# datalogger.net
KiCad netlist of a schematic drawn in EAGLE
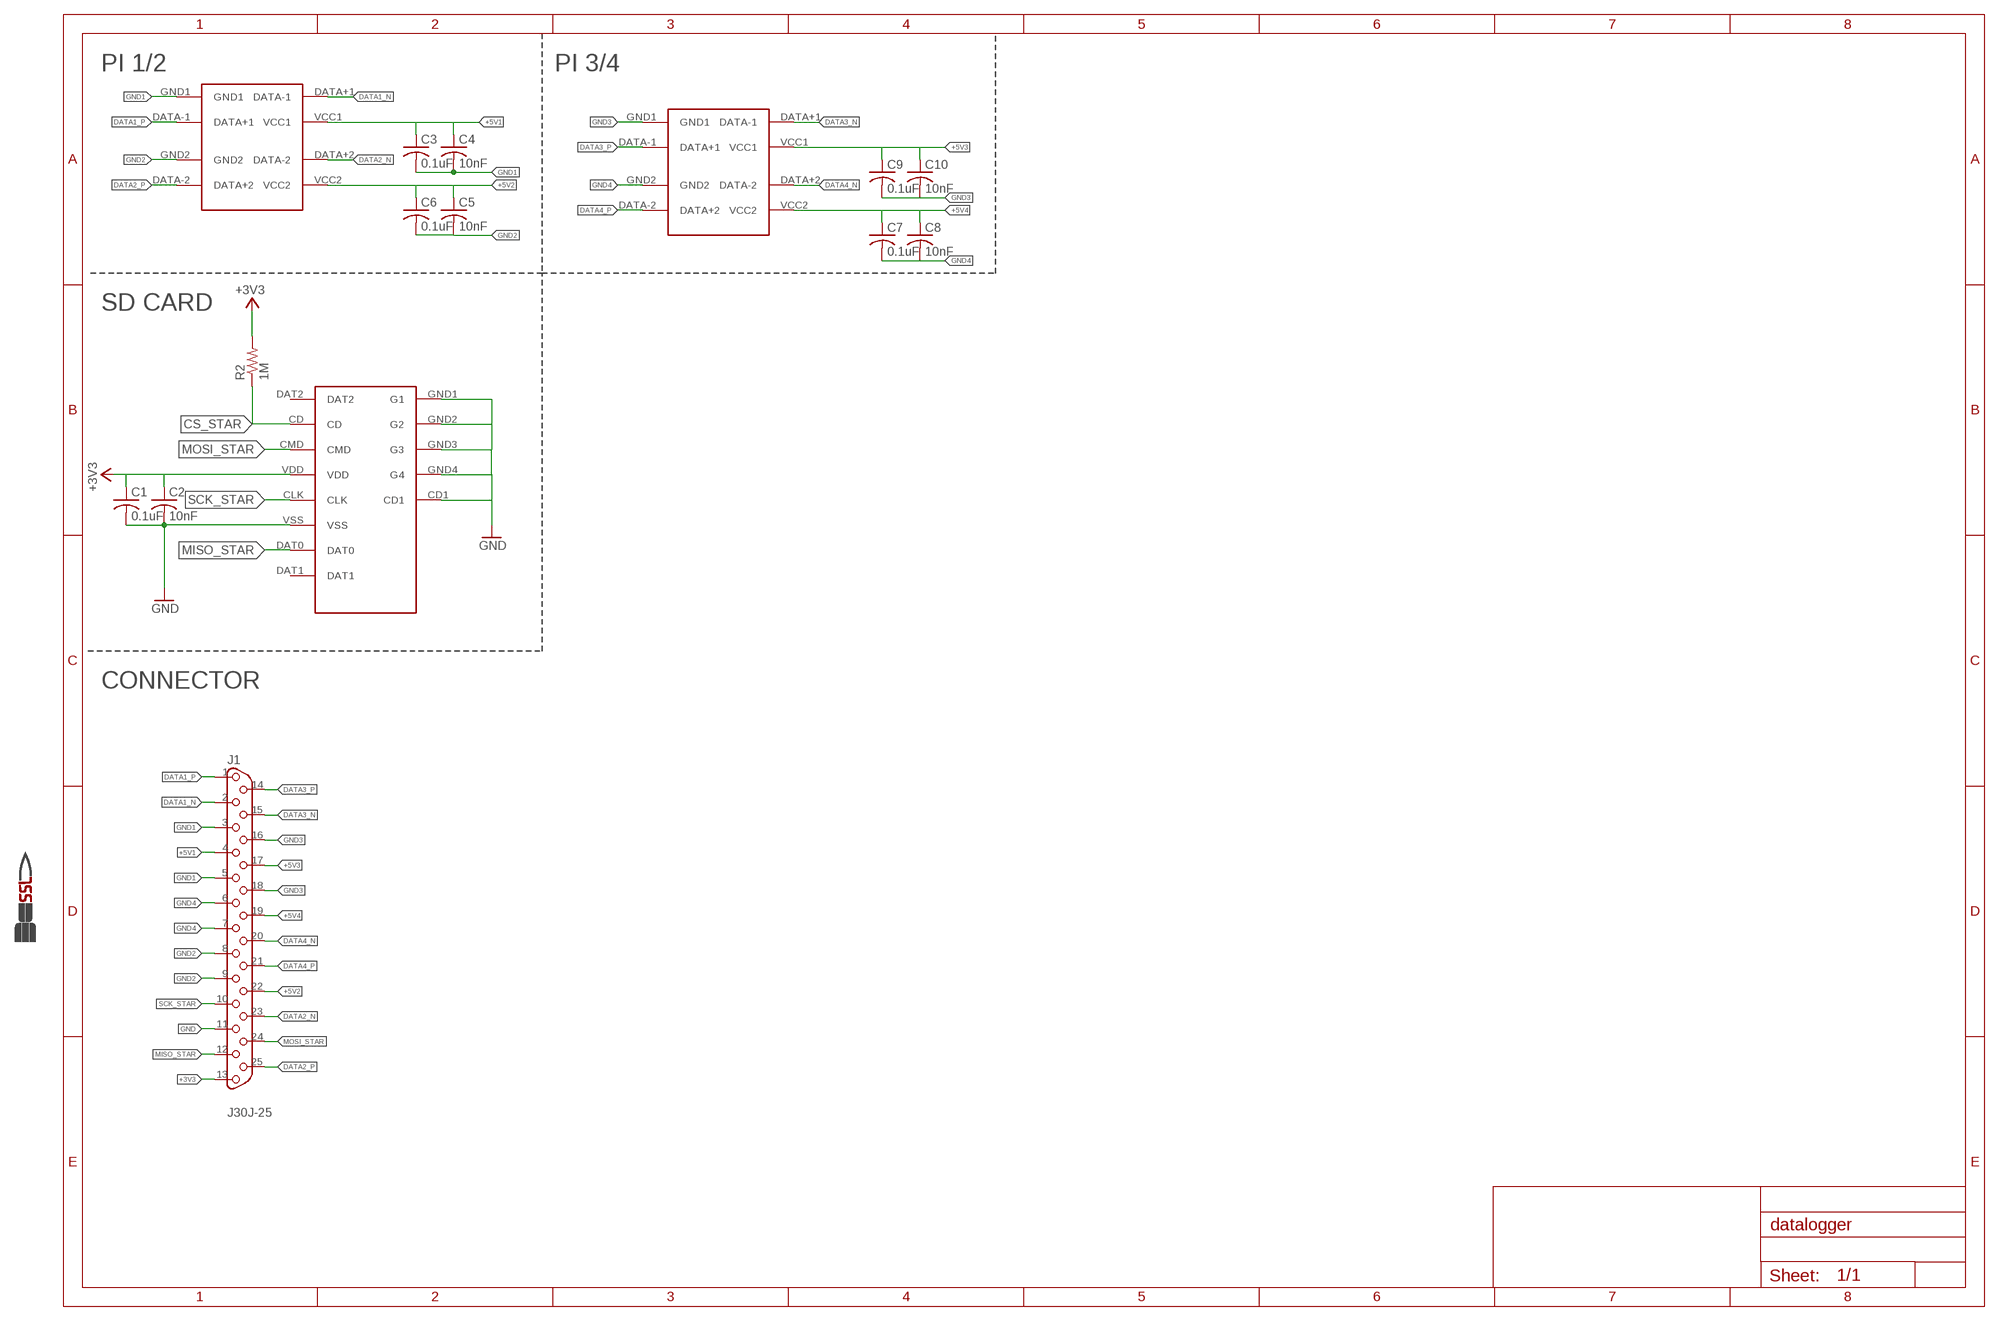
[diagram p0: schematic, sheet 1]

(export (version "E")
  (design (tool "Eeschema 10.0.6"))
  (components
    (comp (ref "C1")
      (value "0.1uF")
      (footprint "eagle-import:C0603")
      (libsource (lib "eagle-import") (part "C-USC0603"))
    )
    (comp (ref "C2")
      (value "10nF")
      (footprint "eagle-import:C0603")
      (libsource (lib "eagle-import") (part "C-USC0603"))
    )
    (comp (ref "C3")
      (value "0.1uF")
      (footprint "eagle-import:C0603")
      (libsource (lib "eagle-import") (part "C-USC0603"))
    )
    (comp (ref "C4")
      (value "10nF")
      (footprint "eagle-import:C0603")
      (libsource (lib "eagle-import") (part "C-USC0603"))
    )
    (comp (ref "C5")
      (value "10nF")
      (footprint "eagle-import:C0603")
      (libsource (lib "eagle-import") (part "C-USC0603"))
    )
    (comp (ref "C6")
      (value "0.1uF")
      (footprint "eagle-import:C0603")
      (libsource (lib "eagle-import") (part "C-USC0603"))
    )
    (comp (ref "C7")
      (value "0.1uF")
      (footprint "eagle-import:C0603")
      (libsource (lib "eagle-import") (part "C-USC0603"))
    )
    (comp (ref "C8")
      (value "10nF")
      (footprint "eagle-import:C0603")
      (libsource (lib "eagle-import") (part "C-USC0603"))
    )
    (comp (ref "C9")
      (value "0.1uF")
      (footprint "eagle-import:C0603")
      (libsource (lib "eagle-import") (part "C-USC0603"))
    )
    (comp (ref "C10")
      (value "10nF")
      (footprint "eagle-import:C0603")
      (libsource (lib "eagle-import") (part "C-USC0603"))
    )
    (comp (ref "GND1")
      (value "SSL.3IN_SILK")
      (footprint "eagle-import:SSL_SILK_.3IN")
      (libsource (lib "eagle-import") (part "SSL.3IN_SILK"))
    )
    (comp (ref "J1")
      (value "J30J-25")
      (footprint "eagle-import:ZKN-25")
      (libsource (lib "eagle-import") (part "J30J-25"))
    )
    (comp (ref "R2")
      (value "1M")
      (footprint "eagle-import:R0603")
      (libsource (lib "eagle-import") (part "R-US_R0603"))
    )
    (comp (ref "U$1")
      (value "MICRO_SD")
      (footprint "eagle-import:MICRO_SD_HINGED")
      (libsource (lib "eagle-import") (part "MICRO_SD"))
    )
    (comp (ref "U$2")
      (value "USB_A")
      (footprint "eagle-import:USB_A")
      (libsource (lib "eagle-import") (part "USB_A"))
    )
    (comp (ref "U$3")
      (value "USB_A")
      (footprint "eagle-import:USB_A")
      (libsource (lib "eagle-import") (part "USB_A"))
    )
  )
  (nets
    (net (code "1") (name "+3V3") (class "Default")
      (node (ref "C1") (pin "1") (pinfunction "1_1") (pintype "passive"))
      (node (ref "C2") (pin "1") (pinfunction "1_1") (pintype "passive"))
      (node (ref "J1") (pin "13") (pinfunction "13_13") (pintype "bidirectional"))
      (node (ref "R2") (pin "2") (pinfunction "2_2") (pintype "passive"))
      (node (ref "U$1") (pin "VDD") (pinfunction "VDD_VDD") (pintype "bidirectional"))
    )
    (net (code "2") (name "+5V1") (class "Default")
      (node (ref "C3") (pin "1") (pinfunction "1_1") (pintype "passive"))
      (node (ref "C4") (pin "1") (pinfunction "1_1") (pintype "passive"))
      (node (ref "J1") (pin "4") (pinfunction "4_4") (pintype "bidirectional"))
      (node (ref "U$2") (pin "VCC1") (pinfunction "VCC1_VCC1") (pintype "bidirectional"))
    )
    (net (code "3") (name "+5V2") (class "Default")
      (node (ref "C5") (pin "1") (pinfunction "1_1") (pintype "passive"))
      (node (ref "C6") (pin "1") (pinfunction "1_1") (pintype "passive"))
      (node (ref "J1") (pin "22") (pinfunction "22_22") (pintype "bidirectional"))
      (node (ref "U$2") (pin "VCC2") (pinfunction "VCC2_VCC2") (pintype "bidirectional"))
    )
    (net (code "4") (name "+5V3") (class "Default")
      (node (ref "C10") (pin "1") (pinfunction "1_1") (pintype "passive"))
      (node (ref "C9") (pin "1") (pinfunction "1_1") (pintype "passive"))
      (node (ref "J1") (pin "17") (pinfunction "17_17") (pintype "bidirectional"))
      (node (ref "U$3") (pin "VCC1") (pinfunction "VCC1_VCC1") (pintype "bidirectional"))
    )
    (net (code "5") (name "+5V4") (class "Default")
      (node (ref "C7") (pin "1") (pinfunction "1_1") (pintype "passive"))
      (node (ref "C8") (pin "1") (pinfunction "1_1") (pintype "passive"))
      (node (ref "J1") (pin "19") (pinfunction "19_19") (pintype "bidirectional"))
      (node (ref "U$3") (pin "VCC2") (pinfunction "VCC2_VCC2") (pintype "bidirectional"))
    )
    (net (code "6") (name "CS_STAR") (class "Default")
      (node (ref "R2") (pin "1") (pinfunction "1_1") (pintype "passive"))
      (node (ref "U$1") (pin "CD") (pinfunction "CD_CD") (pintype "bidirectional"))
    )
    (net (code "7") (name "DATA1_N") (class "Default")
      (node (ref "J1") (pin "2") (pinfunction "2_2") (pintype "bidirectional"))
      (node (ref "U$2") (pin "DATA+1") (pinfunction "DATA-1_DATA+1") (pintype "bidirectional"))
    )
    (net (code "8") (name "DATA1_P") (class "Default")
      (node (ref "J1") (pin "1") (pinfunction "1_1") (pintype "bidirectional"))
      (node (ref "U$2") (pin "DATA-1") (pinfunction "DATA+1_DATA-1") (pintype "bidirectional"))
    )
    (net (code "9") (name "DATA2_N") (class "Default")
      (node (ref "J1") (pin "23") (pinfunction "23_23") (pintype "bidirectional"))
      (node (ref "U$2") (pin "DATA+2") (pinfunction "DATA-2_DATA+2") (pintype "bidirectional"))
    )
    (net (code "10") (name "DATA2_P") (class "Default")
      (node (ref "J1") (pin "25") (pinfunction "25_25") (pintype "bidirectional"))
      (node (ref "U$2") (pin "DATA-2") (pinfunction "DATA+2_DATA-2") (pintype "bidirectional"))
    )
    (net (code "11") (name "DATA3_N") (class "Default")
      (node (ref "J1") (pin "15") (pinfunction "15_15") (pintype "bidirectional"))
      (node (ref "U$3") (pin "DATA+1") (pinfunction "DATA-1_DATA+1") (pintype "bidirectional"))
    )
    (net (code "12") (name "DATA3_P") (class "Default")
      (node (ref "J1") (pin "14") (pinfunction "14_14") (pintype "bidirectional"))
      (node (ref "U$3") (pin "DATA-1") (pinfunction "DATA+1_DATA-1") (pintype "bidirectional"))
    )
    (net (code "13") (name "DATA4_N") (class "Default")
      (node (ref "J1") (pin "20") (pinfunction "20_20") (pintype "bidirectional"))
      (node (ref "U$3") (pin "DATA+2") (pinfunction "DATA-2_DATA+2") (pintype "bidirectional"))
    )
    (net (code "14") (name "DATA4_P") (class "Default")
      (node (ref "J1") (pin "21") (pinfunction "21_21") (pintype "bidirectional"))
      (node (ref "U$3") (pin "DATA-2") (pinfunction "DATA+2_DATA-2") (pintype "bidirectional"))
    )
    (net (code "15") (name "GND") (class "Default")
      (node (ref "C1") (pin "2") (pinfunction "2_2") (pintype "passive"))
      (node (ref "C2") (pin "2") (pinfunction "2_2") (pintype "passive"))
      (node (ref "J1") (pin "11") (pinfunction "11_11") (pintype "bidirectional"))
      (node (ref "U$1") (pin "CD1") (pinfunction "CD1_CD1") (pintype "bidirectional"))
      (node (ref "U$1") (pin "GND1") (pinfunction "G1_GND1") (pintype "bidirectional"))
      (node (ref "U$1") (pin "GND2") (pinfunction "G2_GND2") (pintype "bidirectional"))
      (node (ref "U$1") (pin "GND3") (pinfunction "G3_GND3") (pintype "bidirectional"))
      (node (ref "U$1") (pin "GND4") (pinfunction "G4_GND4") (pintype "bidirectional"))
      (node (ref "U$1") (pin "VSS") (pinfunction "VSS_VSS") (pintype "bidirectional"))
    )
    (net (code "16") (name "GND1") (class "Default")
      (node (ref "C3") (pin "2") (pinfunction "2_2") (pintype "passive"))
      (node (ref "C4") (pin "2") (pinfunction "2_2") (pintype "passive"))
      (node (ref "J1") (pin "3") (pinfunction "3_3") (pintype "bidirectional"))
      (node (ref "J1") (pin "5") (pinfunction "5_5") (pintype "bidirectional"))
      (node (ref "U$2") (pin "GND1") (pinfunction "GND1_GND1") (pintype "bidirectional"))
    )
    (net (code "17") (name "GND2") (class "Default")
      (node (ref "C5") (pin "2") (pinfunction "2_2") (pintype "passive"))
      (node (ref "C6") (pin "2") (pinfunction "2_2") (pintype "passive"))
      (node (ref "J1") (pin "8") (pinfunction "8_8") (pintype "bidirectional"))
      (node (ref "J1") (pin "9") (pinfunction "9_9") (pintype "bidirectional"))
      (node (ref "U$2") (pin "GND2") (pinfunction "GND2_GND2") (pintype "bidirectional"))
    )
    (net (code "18") (name "GND3") (class "Default")
      (node (ref "C10") (pin "2") (pinfunction "2_2") (pintype "passive"))
      (node (ref "C9") (pin "2") (pinfunction "2_2") (pintype "passive"))
      (node (ref "J1") (pin "16") (pinfunction "16_16") (pintype "bidirectional"))
      (node (ref "J1") (pin "18") (pinfunction "18_18") (pintype "bidirectional"))
      (node (ref "U$3") (pin "GND1") (pinfunction "GND1_GND1") (pintype "bidirectional"))
    )
    (net (code "19") (name "GND4") (class "Default")
      (node (ref "C7") (pin "2") (pinfunction "2_2") (pintype "passive"))
      (node (ref "C8") (pin "2") (pinfunction "2_2") (pintype "passive"))
      (node (ref "J1") (pin "6") (pinfunction "6_6") (pintype "bidirectional"))
      (node (ref "J1") (pin "7") (pinfunction "7_7") (pintype "bidirectional"))
      (node (ref "U$3") (pin "GND2") (pinfunction "GND2_GND2") (pintype "bidirectional"))
    )
    (net (code "20") (name "MISO_STAR") (class "Default")
      (node (ref "J1") (pin "12") (pinfunction "12_12") (pintype "bidirectional"))
      (node (ref "U$1") (pin "DAT0") (pinfunction "DAT0_DAT0") (pintype "bidirectional"))
    )
    (net (code "21") (name "MOSI_STAR") (class "Default")
      (node (ref "J1") (pin "24") (pinfunction "24_24") (pintype "bidirectional"))
      (node (ref "U$1") (pin "CMD") (pinfunction "CMD_CMD") (pintype "bidirectional"))
    )
    (net (code "22") (name "SCK_STAR") (class "Default")
      (node (ref "J1") (pin "10") (pinfunction "10_10") (pintype "bidirectional"))
      (node (ref "U$1") (pin "CLK") (pinfunction "CLK_CLK") (pintype "bidirectional"))
    )
    (net (code "23") (name "unconnected-(U$1-PadDAT1)") (class "Default")
      (node (ref "U$1") (pin "DAT1") (pinfunction "DAT1_DAT1") (pintype "bidirectional"))
    )
    (net (code "24") (name "unconnected-(U$1-PadDAT2)") (class "Default")
      (node (ref "U$1") (pin "DAT2") (pinfunction "DAT2_DAT2") (pintype "bidirectional"))
    )
  )
)
